# Smart_power_box.net
KiCad netlist of a schematic drawn in EAGLE
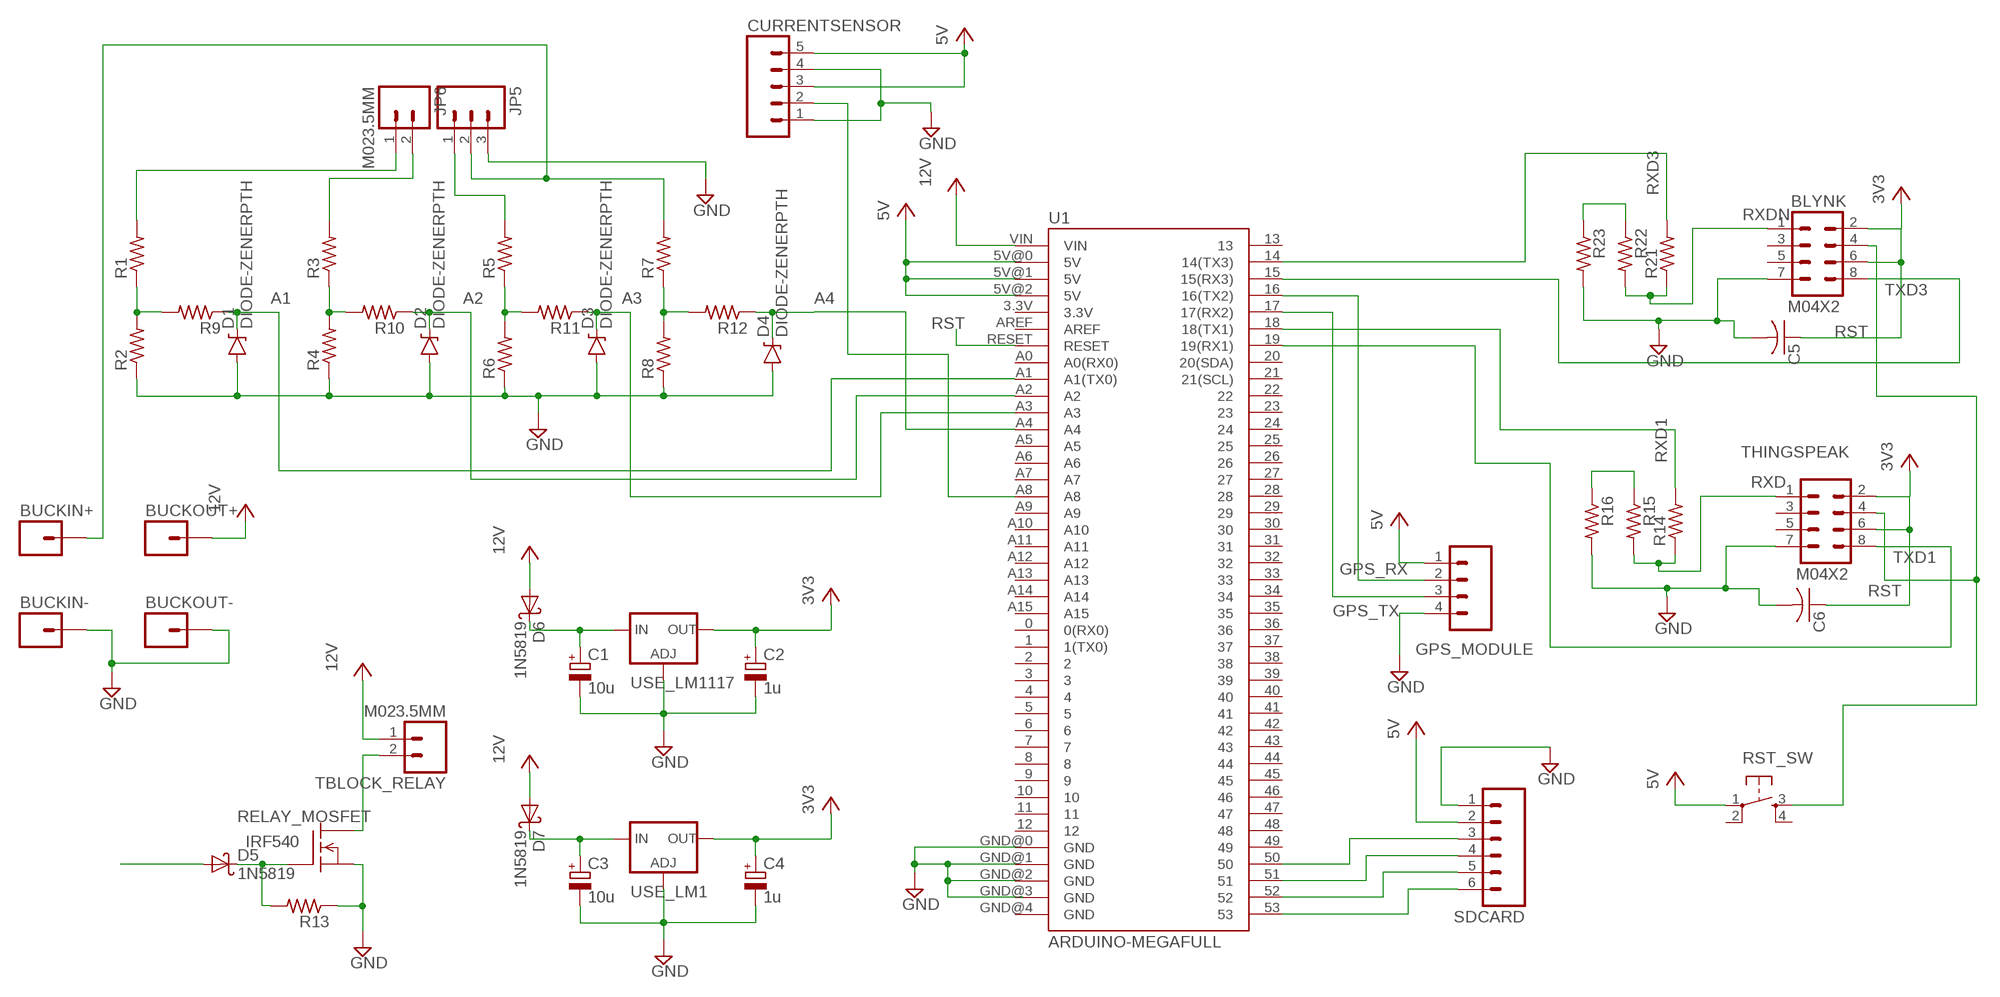
[diagram p0: schematic, sheet 1]

(export (version "E")
  (design (tool "Eeschema 10.0.6"))
  (components
    (comp (ref "BLYNK")
      (value "M04X2")
      (footprint "eagle-import:2X4")
      (libsource (lib "eagle-import") (part "M04X2"))
    )
    (comp (ref "BUCKIN+")
      (value "M01NOSILK-KIT")
      (footprint "eagle-import:1X01NS-KIT")
      (libsource (lib "eagle-import") (part "M01NOSILK-KIT"))
    )
    (comp (ref "BUCKIN-")
      (value "M01NOSILK-KIT")
      (footprint "eagle-import:1X01NS-KIT")
      (libsource (lib "eagle-import") (part "M01NOSILK-KIT"))
    )
    (comp (ref "BUCKOUT+")
      (value "M01NOSILK-KIT")
      (footprint "eagle-import:1X01NS-KIT")
      (libsource (lib "eagle-import") (part "M01NOSILK-KIT"))
    )
    (comp (ref "BUCKOUT-")
      (value "M01NOSILK-KIT")
      (footprint "eagle-import:1X01NS-KIT")
      (libsource (lib "eagle-import") (part "M01NOSILK-KIT"))
    )
    (comp (ref "C1")
      (value "10u")
      (footprint "eagle-import:E2,5-6")
      (libsource (lib "eagle-import") (part "CPOL-EUE2.5-6"))
    )
    (comp (ref "C2")
      (value "1u")
      (footprint "eagle-import:E2,5-6")
      (libsource (lib "eagle-import") (part "CPOL-EUE2.5-6"))
    )
    (comp (ref "C3")
      (value "10u")
      (footprint "eagle-import:E2,5-6")
      (libsource (lib "eagle-import") (part "CPOL-EUE2.5-6"))
    )
    (comp (ref "C4")
      (value "1u")
      (footprint "eagle-import:E2,5-6")
      (libsource (lib "eagle-import") (part "CPOL-EUE2.5-6"))
    )
    (comp (ref "C5")
      (value "C-US025-024X044")
      (footprint "eagle-import:C025-024X044")
      (libsource (lib "eagle-import") (part "C-US025-024X044"))
    )
    (comp (ref "C6")
      (value "C-US025-024X044")
      (footprint "eagle-import:C025-024X044")
      (libsource (lib "eagle-import") (part "C-US025-024X044"))
    )
    (comp (ref "CURRENTSENSOR")
      (value "M05JST-VERT")
      (footprint "eagle-import:JST-5-PTH-VERT")
      (libsource (lib "eagle-import") (part "M05JST-VERT"))
    )
    (comp (ref "D1")
      (value "DIODE-ZENERPTH")
      (footprint "eagle-import:DIODE-ZENER")
      (libsource (lib "eagle-import") (part "DIODE-ZENERPTH"))
    )
    (comp (ref "D2")
      (value "DIODE-ZENERPTH")
      (footprint "eagle-import:DIODE-ZENER")
      (libsource (lib "eagle-import") (part "DIODE-ZENERPTH"))
    )
    (comp (ref "D3")
      (value "DIODE-ZENERPTH")
      (footprint "eagle-import:DIODE-ZENER")
      (libsource (lib "eagle-import") (part "DIODE-ZENERPTH"))
    )
    (comp (ref "D4")
      (value "DIODE-ZENERPTH")
      (footprint "eagle-import:DIODE-ZENER")
      (libsource (lib "eagle-import") (part "DIODE-ZENERPTH"))
    )
    (comp (ref "D5")
      (value "1N5819")
      (footprint "eagle-import:DO41-10")
      (libsource (lib "eagle-import") (part "1N5819"))
    )
    (comp (ref "D6")
      (value "1N5819")
      (footprint "eagle-import:DO41-10")
      (libsource (lib "eagle-import") (part "1N5819"))
    )
    (comp (ref "D7")
      (value "1N5819")
      (footprint "eagle-import:DO41-10")
      (libsource (lib "eagle-import") (part "1N5819"))
    )
    (comp (ref "GPS_MODULE")
      (value "M04PTH")
      (footprint "eagle-import:1X04")
      (libsource (lib "eagle-import") (part "M04PTH"))
    )
    (comp (ref "JP5")
      (value "M03SCREW")
      (footprint "eagle-import:SCREWTERMINAL-3.5MM-3")
      (libsource (lib "eagle-import") (part "M03SCREW"))
    )
    (comp (ref "JP6")
      (value "M023.5MM")
      (footprint "eagle-import:SCREWTERMINAL-3.5MM-2")
      (libsource (lib "eagle-import") (part "M023.5MM"))
    )
    (comp (ref "R1")
      (value "R-US_0207/15")
      (footprint "eagle-import:0207_15")
      (libsource (lib "eagle-import") (part "resistor_R-US_0207/15"))
    )
    (comp (ref "R2")
      (value "R-US_0207/15")
      (footprint "eagle-import:0207_15")
      (libsource (lib "eagle-import") (part "resistor_R-US_0207/15"))
    )
    (comp (ref "R3")
      (value "R-US_0207/15")
      (footprint "eagle-import:0207_15")
      (libsource (lib "eagle-import") (part "resistor_R-US_0207/15"))
    )
    (comp (ref "R4")
      (value "R-US_0207/15")
      (footprint "eagle-import:0207_15")
      (libsource (lib "eagle-import") (part "resistor_R-US_0207/15"))
    )
    (comp (ref "R5")
      (value "R-US_0207/15")
      (footprint "eagle-import:0207_15")
      (libsource (lib "eagle-import") (part "resistor_R-US_0207/15"))
    )
    (comp (ref "R6")
      (value "R-US_0207/15")
      (footprint "eagle-import:0207_15")
      (libsource (lib "eagle-import") (part "resistor_R-US_0207/15"))
    )
    (comp (ref "R7")
      (value "R-US_0207/15")
      (footprint "eagle-import:0207_15")
      (libsource (lib "eagle-import") (part "resistor_R-US_0207/15"))
    )
    (comp (ref "R8")
      (value "R-US_0207/15")
      (footprint "eagle-import:0207_15")
      (libsource (lib "eagle-import") (part "resistor_R-US_0207/15"))
    )
    (comp (ref "R9")
      (value "R-US_0207/15")
      (footprint "eagle-import:0207_15")
      (libsource (lib "eagle-import") (part "resistor_R-US_0207/15"))
    )
    (comp (ref "R10")
      (value "R-US_0207/15")
      (footprint "eagle-import:0207_15")
      (libsource (lib "eagle-import") (part "resistor_R-US_0207/15"))
    )
    (comp (ref "R11")
      (value "R-US_0207/15")
      (footprint "eagle-import:0207_15")
      (libsource (lib "eagle-import") (part "resistor_R-US_0207/15"))
    )
    (comp (ref "R12")
      (value "R-US_0207/15")
      (footprint "eagle-import:0207_15")
      (libsource (lib "eagle-import") (part "resistor_R-US_0207/15"))
    )
    (comp (ref "R13")
      (value "R-US_0207/7")
      (footprint "eagle-import:0207_7")
      (libsource (lib "eagle-import") (part "R-US_0207/7"))
    )
    (comp (ref "R14")
      (value "R-US_0207/7")
      (footprint "eagle-import:0207_7")
      (libsource (lib "eagle-import") (part "R-US_0207/7"))
    )
    (comp (ref "R15")
      (value "R-US_0207/7")
      (footprint "eagle-import:0207_7")
      (libsource (lib "eagle-import") (part "R-US_0207/7"))
    )
    (comp (ref "R16")
      (value "R-US_0207/7")
      (footprint "eagle-import:0207_7")
      (libsource (lib "eagle-import") (part "R-US_0207/7"))
    )
    (comp (ref "R21")
      (value "R-US_0207/7")
      (footprint "eagle-import:0207_7")
      (libsource (lib "eagle-import") (part "R-US_0207/7"))
    )
    (comp (ref "R22")
      (value "R-US_0207/7")
      (footprint "eagle-import:0207_7")
      (libsource (lib "eagle-import") (part "R-US_0207/7"))
    )
    (comp (ref "R23")
      (value "R-US_0207/7")
      (footprint "eagle-import:0207_7")
      (libsource (lib "eagle-import") (part "R-US_0207/7"))
    )
    (comp (ref "RELAY_MOSFET")
      (value "IRF540")
      (footprint "eagle-import:TO220")
      (libsource (lib "eagle-import") (part "IRF540"))
    )
    (comp (ref "RST_SW")
      (value "OMRON_SWITCH_40-XX")
      (footprint "eagle-import:B3F-40XX")
      (libsource (lib "eagle-import") (part "OMRON_SWITCH_40-XX"))
    )
    (comp (ref "SDCARD")
      (value "M06SILK_FEMALE_PTH")
      (footprint "eagle-import:1X06")
      (libsource (lib "eagle-import") (part "M06SILK_FEMALE_PTH"))
    )
    (comp (ref "TBLOCK_RELAY")
      (value "M023.5MM")
      (footprint "eagle-import:SCREWTERMINAL-3.5MM-2")
      (libsource (lib "eagle-import") (part "M023.5MM"))
    )
    (comp (ref "THINGSPEAK")
      (value "M04X2")
      (footprint "eagle-import:2X4")
      (libsource (lib "eagle-import") (part "M04X2"))
    )
    (comp (ref "U1")
      (value "ARDUINO-MEGAFULL")
      (footprint "eagle-import:ARDUINO_MEGA")
      (libsource (lib "eagle-import") (part "ARDUINO-MEGAFULL"))
    )
    (comp (ref "USE_LM1")
      (value "V_REG_317SINK")
      (footprint "eagle-import:TO220-ADJ")
      (libsource (lib "eagle-import") (part "V_REG_317SINK"))
    )
    (comp (ref "USE_LM1117")
      (value "V_REG_317SINK")
      (footprint "eagle-import:TO220-ADJ")
      (libsource (lib "eagle-import") (part "V_REG_317SINK"))
    )
  )
  (nets
    (net (code "1") (name "/A1") (class "Default")
      (node (ref "D1") (pin "P$1") (pinfunction "C_P$1") (pintype "passive"))
      (node (ref "R9") (pin "1") (pinfunction "1_1") (pintype "passive"))
      (node (ref "U1") (pin "A1") (pinfunction "A1(TX0)_A1") (pintype "bidirectional"))
    )
    (net (code "2") (name "/A2") (class "Default")
      (node (ref "D2") (pin "P$1") (pinfunction "C_P$1") (pintype "passive"))
      (node (ref "R10") (pin "1") (pinfunction "1_1") (pintype "passive"))
      (node (ref "U1") (pin "A2") (pinfunction "A2_A2") (pintype "bidirectional"))
    )
    (net (code "3") (name "/A3") (class "Default")
      (node (ref "D3") (pin "P$1") (pinfunction "C_P$1") (pintype "passive"))
      (node (ref "R11") (pin "1") (pinfunction "1_1") (pintype "passive"))
      (node (ref "U1") (pin "A3") (pinfunction "A3_A3") (pintype "bidirectional"))
    )
    (net (code "4") (name "/A4") (class "Default")
      (node (ref "D4") (pin "P$1") (pinfunction "C_P$1") (pintype "passive"))
      (node (ref "R12") (pin "1") (pinfunction "1_1") (pintype "passive"))
      (node (ref "U1") (pin "A4") (pinfunction "A4_A4") (pintype "bidirectional"))
    )
    (net (code "5") (name "/GPS_RX") (class "Default")
      (node (ref "GPS_MODULE") (pin "2") (pinfunction "2_2") (pintype "passive"))
      (node (ref "U1") (pin "16") (pinfunction "16(TX2)_16") (pintype "bidirectional"))
    )
    (net (code "6") (name "/GPS_TX") (class "Default")
      (node (ref "GPS_MODULE") (pin "3") (pinfunction "3_3") (pintype "passive"))
      (node (ref "U1") (pin "17") (pinfunction "17(RX2)_17") (pintype "bidirectional"))
    )
    (net (code "7") (name "/RST") (class "Default")
      (node (ref "BLYNK") (pin "4") (pinfunction "4_4") (pintype "passive"))
      (node (ref "RST_SW") (pin "3") (pinfunction "S_3") (pintype "passive"))
      (node (ref "THINGSPEAK") (pin "4") (pinfunction "4_4") (pintype "passive"))
      (node (ref "U1") (pin "RESET") (pinfunction "RESET_RESET") (pintype "bidirectional"))
    )
    (net (code "8") (name "/RXD") (class "Default")
      (node (ref "R14") (pin "1") (pinfunction "1_1") (pintype "passive"))
      (node (ref "R15") (pin "2") (pinfunction "2_2") (pintype "passive"))
      (node (ref "THINGSPEAK") (pin "1") (pinfunction "1_1") (pintype "passive"))
    )
    (net (code "9") (name "/RXD1") (class "Default")
      (node (ref "R14") (pin "2") (pinfunction "2_2") (pintype "passive"))
      (node (ref "U1") (pin "18") (pinfunction "18(TX1)_18") (pintype "bidirectional"))
    )
    (net (code "10") (name "/RXD3") (class "Default")
      (node (ref "R21") (pin "2") (pinfunction "2_2") (pintype "passive"))
      (node (ref "U1") (pin "14") (pinfunction "14(TX3)_14") (pintype "bidirectional"))
    )
    (net (code "11") (name "/RXDN") (class "Default")
      (node (ref "BLYNK") (pin "1") (pinfunction "1_1") (pintype "passive"))
      (node (ref "R21") (pin "1") (pinfunction "1_1") (pintype "passive"))
      (node (ref "R22") (pin "2") (pinfunction "2_2") (pintype "passive"))
    )
    (net (code "12") (name "/TXD1") (class "Default")
      (node (ref "THINGSPEAK") (pin "8") (pinfunction "8_8") (pintype "passive"))
      (node (ref "U1") (pin "19") (pinfunction "19(RX1)_19") (pintype "bidirectional"))
    )
    (net (code "13") (name "/TXD3") (class "Default")
      (node (ref "BLYNK") (pin "8") (pinfunction "8_8") (pintype "passive"))
      (node (ref "U1") (pin "15") (pinfunction "15(RX3)_15") (pintype "bidirectional"))
    )
    (net (code "14") (name "12V") (class "Default")
      (node (ref "BLYNK") (pin "2") (pinfunction "2_2") (pintype "passive"))
      (node (ref "BLYNK") (pin "6") (pinfunction "6_6") (pintype "passive"))
      (node (ref "BUCKOUT+") (pin "1") (pinfunction "1_1") (pintype "passive"))
      (node (ref "C2") (pin "+") (pinfunction "+_+") (pintype "passive"))
      (node (ref "C4") (pin "+") (pinfunction "+_+") (pintype "passive"))
      (node (ref "C5") (pin "1") (pinfunction "1_1") (pintype "passive"))
      (node (ref "C6") (pin "1") (pinfunction "1_1") (pintype "passive"))
      (node (ref "CURRENTSENSOR") (pin "3") (pinfunction "3_3") (pintype "passive"))
      (node (ref "CURRENTSENSOR") (pin "5") (pinfunction "5_5") (pintype "passive"))
      (node (ref "D6") (pin "A") (pinfunction "A_A") (pintype "passive"))
      (node (ref "D7") (pin "A") (pinfunction "A_A") (pintype "passive"))
      (node (ref "GPS_MODULE") (pin "1") (pinfunction "1_1") (pintype "passive"))
      (node (ref "RST_SW") (pin "1") (pinfunction "P_1") (pintype "passive"))
      (node (ref "SDCARD") (pin "2") (pinfunction "2_2") (pintype "passive"))
      (node (ref "TBLOCK_RELAY") (pin "1") (pinfunction "1_1") (pintype "passive"))
      (node (ref "THINGSPEAK") (pin "2") (pinfunction "2_2") (pintype "passive"))
      (node (ref "THINGSPEAK") (pin "6") (pinfunction "6_6") (pintype "passive"))
      (node (ref "U1") (pin "5V@0") (pinfunction "5V_5V@0") (pintype "bidirectional"))
      (node (ref "U1") (pin "5V@1") (pinfunction "5V_5V@1") (pintype "bidirectional"))
      (node (ref "U1") (pin "5V@2") (pinfunction "5V_5V@2") (pintype "bidirectional"))
      (node (ref "U1") (pin "VIN") (pinfunction "VIN_VIN") (pintype "bidirectional"))
      (node (ref "USE_LM1") (pin "OUT") (pinfunction "OUT_OUT") (pintype "output"))
      (node (ref "USE_LM1117") (pin "OUT") (pinfunction "OUT_OUT") (pintype "output"))
    )
    (net (code "15") (name "GND") (class "Default")
      (node (ref "BLYNK") (pin "7") (pinfunction "7_7") (pintype "passive"))
      (node (ref "BUCKIN-") (pin "1") (pinfunction "1_1") (pintype "passive"))
      (node (ref "BUCKOUT-") (pin "1") (pinfunction "1_1") (pintype "passive"))
      (node (ref "C1") (pin "-") (pinfunction "-_-") (pintype "passive"))
      (node (ref "C2") (pin "-") (pinfunction "-_-") (pintype "passive"))
      (node (ref "C3") (pin "-") (pinfunction "-_-") (pintype "passive"))
      (node (ref "C4") (pin "-") (pinfunction "-_-") (pintype "passive"))
      (node (ref "C5") (pin "2") (pinfunction "2_2") (pintype "passive"))
      (node (ref "C6") (pin "2") (pinfunction "2_2") (pintype "passive"))
      (node (ref "CURRENTSENSOR") (pin "1") (pinfunction "1_1") (pintype "passive"))
      (node (ref "CURRENTSENSOR") (pin "4") (pinfunction "4_4") (pintype "passive"))
      (node (ref "D1") (pin "P$2") (pinfunction "A_P$2") (pintype "passive"))
      (node (ref "D2") (pin "P$2") (pinfunction "A_P$2") (pintype "passive"))
      (node (ref "D3") (pin "P$2") (pinfunction "A_P$2") (pintype "passive"))
      (node (ref "D4") (pin "P$2") (pinfunction "A_P$2") (pintype "passive"))
      (node (ref "GPS_MODULE") (pin "4") (pinfunction "4_4") (pintype "passive"))
      (node (ref "JP5") (pin "3") (pinfunction "3_3") (pintype "passive"))
      (node (ref "R13") (pin "1") (pinfunction "1_1") (pintype "passive"))
      (node (ref "R16") (pin "2") (pinfunction "2_2") (pintype "passive"))
      (node (ref "R2") (pin "1") (pinfunction "1_1") (pintype "passive"))
      (node (ref "R23") (pin "2") (pinfunction "2_2") (pintype "passive"))
      (node (ref "R4") (pin "1") (pinfunction "1_1") (pintype "passive"))
      (node (ref "R6") (pin "1") (pinfunction "1_1") (pintype "passive"))
      (node (ref "R8") (pin "1") (pinfunction "1_1") (pintype "passive"))
      (node (ref "RELAY_MOSFET") (pin "3") (pinfunction "S_3") (pintype "passive"))
      (node (ref "SDCARD") (pin "1") (pinfunction "1_1") (pintype "passive"))
      (node (ref "THINGSPEAK") (pin "7") (pinfunction "7_7") (pintype "passive"))
      (node (ref "U1") (pin "GND@0") (pinfunction "GND_GND@0") (pintype "bidirectional"))
      (node (ref "U1") (pin "GND@1") (pinfunction "GND_GND@1") (pintype "bidirectional"))
      (node (ref "U1") (pin "GND@2") (pinfunction "GND_GND@2") (pintype "bidirectional"))
      (node (ref "USE_LM1") (pin "ADJ") (pinfunction "ADJ_ADJ") (pintype "input"))
      (node (ref "USE_LM1117") (pin "ADJ") (pinfunction "ADJ_ADJ") (pintype "input"))
    )
    (net (code "16") (name "Net-(BUCKIN+-Pad1)") (class "Default")
      (node (ref "BUCKIN+") (pin "1") (pinfunction "1_1") (pintype "passive"))
      (node (ref "JP5") (pin "2") (pinfunction "2_2") (pintype "passive"))
      (node (ref "R7") (pin "2") (pinfunction "2_2") (pintype "passive"))
    )
    (net (code "17") (name "Net-(C1-Pad+)") (class "Default")
      (node (ref "C1") (pin "+") (pinfunction "+_+") (pintype "passive"))
      (node (ref "D6") (pin "C") (pinfunction "C_C") (pintype "passive"))
      (node (ref "USE_LM1117") (pin "IN") (pinfunction "IN_IN") (pintype "input"))
    )
    (net (code "18") (name "Net-(C3-Pad+)") (class "Default")
      (node (ref "C3") (pin "+") (pinfunction "+_+") (pintype "passive"))
      (node (ref "D7") (pin "C") (pinfunction "C_C") (pintype "passive"))
      (node (ref "USE_LM1") (pin "IN") (pinfunction "IN_IN") (pintype "input"))
    )
    (net (code "19") (name "Net-(CURRENTSENSOR-Pad2)") (class "Default")
      (node (ref "CURRENTSENSOR") (pin "2") (pinfunction "2_2") (pintype "passive"))
      (node (ref "U1") (pin "A8") (pinfunction "A8_A8") (pintype "bidirectional"))
    )
    (net (code "20") (name "Net-(JP5-Pad1)") (class "Default")
      (node (ref "JP5") (pin "1") (pinfunction "1_1") (pintype "passive"))
      (node (ref "R5") (pin "2") (pinfunction "2_2") (pintype "passive"))
    )
    (net (code "21") (name "Net-(JP6-Pad1)") (class "Default")
      (node (ref "JP6") (pin "1") (pinfunction "1_1") (pintype "passive"))
      (node (ref "R1") (pin "2") (pinfunction "2_2") (pintype "passive"))
    )
    (net (code "22") (name "Net-(JP6-Pad2)") (class "Default")
      (node (ref "JP6") (pin "2") (pinfunction "2_2") (pintype "passive"))
      (node (ref "R3") (pin "2") (pinfunction "2_2") (pintype "passive"))
    )
    (net (code "23") (name "Net-(R1-Pad1)") (class "Default")
      (node (ref "R1") (pin "1") (pinfunction "1_1") (pintype "passive"))
      (node (ref "R2") (pin "2") (pinfunction "2_2") (pintype "passive"))
      (node (ref "R9") (pin "2") (pinfunction "2_2") (pintype "passive"))
    )
    (net (code "24") (name "Net-(R10-Pad2)") (class "Default")
      (node (ref "R10") (pin "2") (pinfunction "2_2") (pintype "passive"))
      (node (ref "R3") (pin "1") (pinfunction "1_1") (pintype "passive"))
      (node (ref "R4") (pin "2") (pinfunction "2_2") (pintype "passive"))
    )
    (net (code "25") (name "Net-(R11-Pad2)") (class "Default")
      (node (ref "R11") (pin "2") (pinfunction "2_2") (pintype "passive"))
      (node (ref "R5") (pin "1") (pinfunction "1_1") (pintype "passive"))
      (node (ref "R6") (pin "2") (pinfunction "2_2") (pintype "passive"))
    )
    (net (code "26") (name "Net-(R12-Pad2)") (class "Default")
      (node (ref "R12") (pin "2") (pinfunction "2_2") (pintype "passive"))
      (node (ref "R7") (pin "1") (pinfunction "1_1") (pintype "passive"))
      (node (ref "R8") (pin "2") (pinfunction "2_2") (pintype "passive"))
    )
    (net (code "27") (name "Net-(R15-Pad1)") (class "Default")
      (node (ref "R15") (pin "1") (pinfunction "1_1") (pintype "passive"))
      (node (ref "R16") (pin "1") (pinfunction "1_1") (pintype "passive"))
    )
    (net (code "28") (name "Net-(R22-Pad1)") (class "Default")
      (node (ref "R22") (pin "1") (pinfunction "1_1") (pintype "passive"))
      (node (ref "R23") (pin "1") (pinfunction "1_1") (pintype "passive"))
    )
    (net (code "29") (name "Net-(RELAY_MOSFET-D)") (class "Default")
      (node (ref "RELAY_MOSFET") (pin "2") (pinfunction "D_2") (pintype "passive"))
      (node (ref "TBLOCK_RELAY") (pin "2") (pinfunction "2_2") (pintype "passive"))
    )
    (net (code "30") (name "Net-(RELAY_MOSFET-G)") (class "Default")
      (node (ref "D5") (pin "C") (pinfunction "C_C") (pintype "passive"))
      (node (ref "R13") (pin "2") (pinfunction "2_2") (pintype "passive"))
      (node (ref "RELAY_MOSFET") (pin "1") (pinfunction "G_1") (pintype "passive"))
    )
    (net (code "31") (name "Net-(SDCARD-Pad3)") (class "Default")
      (node (ref "SDCARD") (pin "3") (pinfunction "3_3") (pintype "passive"))
      (node (ref "U1") (pin "50") (pinfunction "50_50") (pintype "bidirectional"))
    )
    (net (code "32") (name "Net-(SDCARD-Pad4)") (class "Default")
      (node (ref "SDCARD") (pin "4") (pinfunction "4_4") (pintype "passive"))
      (node (ref "U1") (pin "51") (pinfunction "51_51") (pintype "bidirectional"))
    )
    (net (code "33") (name "Net-(SDCARD-Pad5)") (class "Default")
      (node (ref "SDCARD") (pin "5") (pinfunction "5_5") (pintype "passive"))
      (node (ref "U1") (pin "52") (pinfunction "52_52") (pintype "bidirectional"))
    )
    (net (code "34") (name "Net-(SDCARD-Pad6)") (class "Default")
      (node (ref "SDCARD") (pin "6") (pinfunction "6_6") (pintype "passive"))
      (node (ref "U1") (pin "53") (pinfunction "53_53") (pintype "bidirectional"))
    )
    (net (code "35") (name "unconnected-(BLYNK-Pad3)") (class "Default")
      (node (ref "BLYNK") (pin "3") (pinfunction "3_3") (pintype "passive"))
    )
    (net (code "36") (name "unconnected-(BLYNK-Pad5)") (class "Default")
      (node (ref "BLYNK") (pin "5") (pinfunction "5_5") (pintype "passive"))
    )
    (net (code "37") (name "unconnected-(D5-PadA)") (class "Default")
      (node (ref "D5") (pin "A") (pinfunction "A_A") (pintype "passive"))
    )
    (net (code "38") (name "unconnected-(RST_SW-P1-Pad2)") (class "Default")
      (node (ref "RST_SW") (pin "2") (pinfunction "P1_2") (pintype "passive"))
    )
    (net (code "39") (name "unconnected-(RST_SW-S1-Pad4)") (class "Default")
      (node (ref "RST_SW") (pin "4") (pinfunction "S1_4") (pintype "passive"))
    )
    (net (code "40") (name "unconnected-(THINGSPEAK-Pad3)") (class "Default")
      (node (ref "THINGSPEAK") (pin "3") (pinfunction "3_3") (pintype "passive"))
    )
    (net (code "41") (name "unconnected-(THINGSPEAK-Pad5)") (class "Default")
      (node (ref "THINGSPEAK") (pin "5") (pinfunction "5_5") (pintype "passive"))
    )
    (net (code "42") (name "unconnected-(U1-0(RX0)-Pad0)") (class "Default")
      (node (ref "U1") (pin "0") (pinfunction "0(RX0)_0") (pintype "bidirectional"))
    )
    (net (code "43") (name "unconnected-(U1-1(TX0)-Pad1)") (class "Default")
      (node (ref "U1") (pin "1") (pinfunction "1(TX0)_1") (pintype "bidirectional"))
    )
    (net (code "44") (name "unconnected-(U1-20(SDA)-Pad20)") (class "Default")
      (node (ref "U1") (pin "20") (pinfunction "20(SDA)_20") (pintype "bidirectional"))
    )
    (net (code "45") (name "unconnected-(U1-21(SCL)-Pad21)") (class "Default")
      (node (ref "U1") (pin "21") (pinfunction "21(SCL)_21") (pintype "bidirectional"))
    )
    (net (code "46") (name "unconnected-(U1-A0(RX0)-PadA0)") (class "Default")
      (node (ref "U1") (pin "A0") (pinfunction "A0(RX0)_A0") (pintype "bidirectional"))
    )
    (net (code "47") (name "unconnected-(U1-GND-PadGND@3)") (class "Default")
      (node (ref "U1") (pin "GND@3") (pinfunction "GND_GND@3") (pintype "bidirectional"))
    )
    (net (code "48") (name "unconnected-(U1-GND-PadGND@4)") (class "Default")
      (node (ref "U1") (pin "GND@4") (pinfunction "GND_GND@4") (pintype "bidirectional"))
    )
    (net (code "49") (name "unconnected-(U1-Pad2)") (class "Default")
      (node (ref "U1") (pin "2") (pinfunction "2_2") (pintype "bidirectional"))
    )
    (net (code "50") (name "unconnected-(U1-Pad3)") (class "Default")
      (node (ref "U1") (pin "3") (pinfunction "3_3") (pintype "bidirectional"))
    )
    (net (code "51") (name "unconnected-(U1-Pad3.3V)") (class "Default")
      (node (ref "U1") (pin "3.3V") (pinfunction "3.3V_3.3V") (pintype "bidirectional"))
    )
    (net (code "52") (name "unconnected-(U1-Pad4)") (class "Default")
      (node (ref "U1") (pin "4") (pinfunction "4_4") (pintype "bidirectional"))
    )
    (net (code "53") (name "unconnected-(U1-Pad5)") (class "Default")
      (node (ref "U1") (pin "5") (pinfunction "5_5") (pintype "bidirectional"))
    )
    (net (code "54") (name "unconnected-(U1-Pad6)") (class "Default")
      (node (ref "U1") (pin "6") (pinfunction "6_6") (pintype "bidirectional"))
    )
    (net (code "55") (name "unconnected-(U1-Pad7)") (class "Default")
      (node (ref "U1") (pin "7") (pinfunction "7_7") (pintype "bidirectional"))
    )
    (net (code "56") (name "unconnected-(U1-Pad8)") (class "Default")
      (node (ref "U1") (pin "8") (pinfunction "8_8") (pintype "bidirectional"))
    )
    (net (code "57") (name "unconnected-(U1-Pad9)") (class "Default")
      (node (ref "U1") (pin "9") (pinfunction "9_9") (pintype "bidirectional"))
    )
    (net (code "58") (name "unconnected-(U1-Pad10)") (class "Default")
      (node (ref "U1") (pin "10") (pinfunction "10_10") (pintype "bidirectional"))
    )
    (net (code "59") (name "unconnected-(U1-Pad11)") (class "Default")
      (node (ref "U1") (pin "11") (pinfunction "11_11") (pintype "bidirectional"))
    )
    (net (code "60") (name "unconnected-(U1-Pad12)") (class "Default")
      (node (ref "U1") (pin "12") (pinfunction "12_12") (pintype "bidirectional"))
    )
    (net (code "61") (name "unconnected-(U1-Pad13)") (class "Default")
      (node (ref "U1") (pin "13") (pinfunction "13_13") (pintype "bidirectional"))
    )
    (net (code "62") (name "unconnected-(U1-Pad22)") (class "Default")
      (node (ref "U1") (pin "22") (pinfunction "22_22") (pintype "bidirectional"))
    )
    (net (code "63") (name "unconnected-(U1-Pad23)") (class "Default")
      (node (ref "U1") (pin "23") (pinfunction "23_23") (pintype "bidirectional"))
    )
    (net (code "64") (name "unconnected-(U1-Pad24)") (class "Default")
      (node (ref "U1") (pin "24") (pinfunction "24_24") (pintype "bidirectional"))
    )
    (net (code "65") (name "unconnected-(U1-Pad25)") (class "Default")
      (node (ref "U1") (pin "25") (pinfunction "25_25") (pintype "bidirectional"))
    )
    (net (code "66") (name "unconnected-(U1-Pad26)") (class "Default")
      (node (ref "U1") (pin "26") (pinfunction "26_26") (pintype "bidirectional"))
    )
    (net (code "67") (name "unconnected-(U1-Pad27)") (class "Default")
      (node (ref "U1") (pin "27") (pinfunction "27_27") (pintype "bidirectional"))
    )
    (net (code "68") (name "unconnected-(U1-Pad28)") (class "Default")
      (node (ref "U1") (pin "28") (pinfunction "28_28") (pintype "bidirectional"))
    )
    (net (code "69") (name "unconnected-(U1-Pad29)") (class "Default")
      (node (ref "U1") (pin "29") (pinfunction "29_29") (pintype "bidirectional"))
    )
    (net (code "70") (name "unconnected-(U1-Pad30)") (class "Default")
      (node (ref "U1") (pin "30") (pinfunction "30_30") (pintype "bidirectional"))
    )
    (net (code "71") (name "unconnected-(U1-Pad31)") (class "Default")
      (node (ref "U1") (pin "31") (pinfunction "31_31") (pintype "bidirectional"))
    )
    (net (code "72") (name "unconnected-(U1-Pad32)") (class "Default")
      (node (ref "U1") (pin "32") (pinfunction "32_32") (pintype "bidirectional"))
    )
    (net (code "73") (name "unconnected-(U1-Pad33)") (class "Default")
      (node (ref "U1") (pin "33") (pinfunction "33_33") (pintype "bidirectional"))
    )
    (net (code "74") (name "unconnected-(U1-Pad34)") (class "Default")
      (node (ref "U1") (pin "34") (pinfunction "34_34") (pintype "bidirectional"))
    )
    (net (code "75") (name "unconnected-(U1-Pad35)") (class "Default")
      (node (ref "U1") (pin "35") (pinfunction "35_35") (pintype "bidirectional"))
    )
    (net (code "76") (name "unconnected-(U1-Pad36)") (class "Default")
      (node (ref "U1") (pin "36") (pinfunction "36_36") (pintype "bidirectional"))
    )
    (net (code "77") (name "unconnected-(U1-Pad37)") (class "Default")
      (node (ref "U1") (pin "37") (pinfunction "37_37") (pintype "bidirectional"))
    )
    (net (code "78") (name "unconnected-(U1-Pad38)") (class "Default")
      (node (ref "U1") (pin "38") (pinfunction "38_38") (pintype "bidirectional"))
    )
    (net (code "79") (name "unconnected-(U1-Pad39)") (class "Default")
      (node (ref "U1") (pin "39") (pinfunction "39_39") (pintype "bidirectional"))
    )
    (net (code "80") (name "unconnected-(U1-Pad40)") (class "Default")
      (node (ref "U1") (pin "40") (pinfunction "40_40") (pintype "bidirectional"))
    )
    (net (code "81") (name "unconnected-(U1-Pad41)") (class "Default")
      (node (ref "U1") (pin "41") (pinfunction "41_41") (pintype "bidirectional"))
    )
    (net (code "82") (name "unconnected-(U1-Pad42)") (class "Default")
      (node (ref "U1") (pin "42") (pinfunction "42_42") (pintype "bidirectional"))
    )
    (net (code "83") (name "unconnected-(U1-Pad43)") (class "Default")
      (node (ref "U1") (pin "43") (pinfunction "43_43") (pintype "bidirectional"))
    )
    (net (code "84") (name "unconnected-(U1-Pad44)") (class "Default")
      (node (ref "U1") (pin "44") (pinfunction "44_44") (pintype "bidirectional"))
    )
    (net (code "85") (name "unconnected-(U1-Pad45)") (class "Default")
      (node (ref "U1") (pin "45") (pinfunction "45_45") (pintype "bidirectional"))
    )
    (net (code "86") (name "unconnected-(U1-Pad46)") (class "Default")
      (node (ref "U1") (pin "46") (pinfunction "46_46") (pintype "bidirectional"))
    )
    (net (code "87") (name "unconnected-(U1-Pad47)") (class "Default")
      (node (ref "U1") (pin "47") (pinfunction "47_47") (pintype "bidirectional"))
    )
    (net (code "88") (name "unconnected-(U1-Pad48)") (class "Default")
      (node (ref "U1") (pin "48") (pinfunction "48_48") (pintype "bidirectional"))
    )
    (net (code "89") (name "unconnected-(U1-Pad49)") (class "Default")
      (node (ref "U1") (pin "49") (pinfunction "49_49") (pintype "bidirectional"))
    )
    (net (code "90") (name "unconnected-(U1-PadA5)") (class "Default")
      (node (ref "U1") (pin "A5") (pinfunction "A5_A5") (pintype "bidirectional"))
    )
    (net (code "91") (name "unconnected-(U1-PadA6)") (class "Default")
      (node (ref "U1") (pin "A6") (pinfunction "A6_A6") (pintype "bidirectional"))
    )
    (net (code "92") (name "unconnected-(U1-PadA7)") (class "Default")
      (node (ref "U1") (pin "A7") (pinfunction "A7_A7") (pintype "bidirectional"))
    )
    (net (code "93") (name "unconnected-(U1-PadA9)") (class "Default")
      (node (ref "U1") (pin "A9") (pinfunction "A9_A9") (pintype "bidirectional"))
    )
    (net (code "94") (name "unconnected-(U1-PadA10)") (class "Default")
      (node (ref "U1") (pin "A10") (pinfunction "A10_A10") (pintype "bidirectional"))
    )
    (net (code "95") (name "unconnected-(U1-PadA11)") (class "Default")
      (node (ref "U1") (pin "A11") (pinfunction "A11_A11") (pintype "bidirectional"))
    )
    (net (code "96") (name "unconnected-(U1-PadA12)") (class "Default")
      (node (ref "U1") (pin "A12") (pinfunction "A12_A12") (pintype "bidirectional"))
    )
    (net (code "97") (name "unconnected-(U1-PadA13)") (class "Default")
      (node (ref "U1") (pin "A13") (pinfunction "A13_A13") (pintype "bidirectional"))
    )
    (net (code "98") (name "unconnected-(U1-PadA14)") (class "Default")
      (node (ref "U1") (pin "A14") (pinfunction "A14_A14") (pintype "bidirectional"))
    )
    (net (code "99") (name "unconnected-(U1-PadA15)") (class "Default")
      (node (ref "U1") (pin "A15") (pinfunction "A15_A15") (pintype "bidirectional"))
    )
    (net (code "100") (name "unconnected-(U1-PadAREF)") (class "Default")
      (node (ref "U1") (pin "AREF") (pinfunction "AREF_AREF") (pintype "bidirectional"))
    )
  )
)
